# imu_evo.net
KiCad netlist of a schematic drawn in Altium Designer
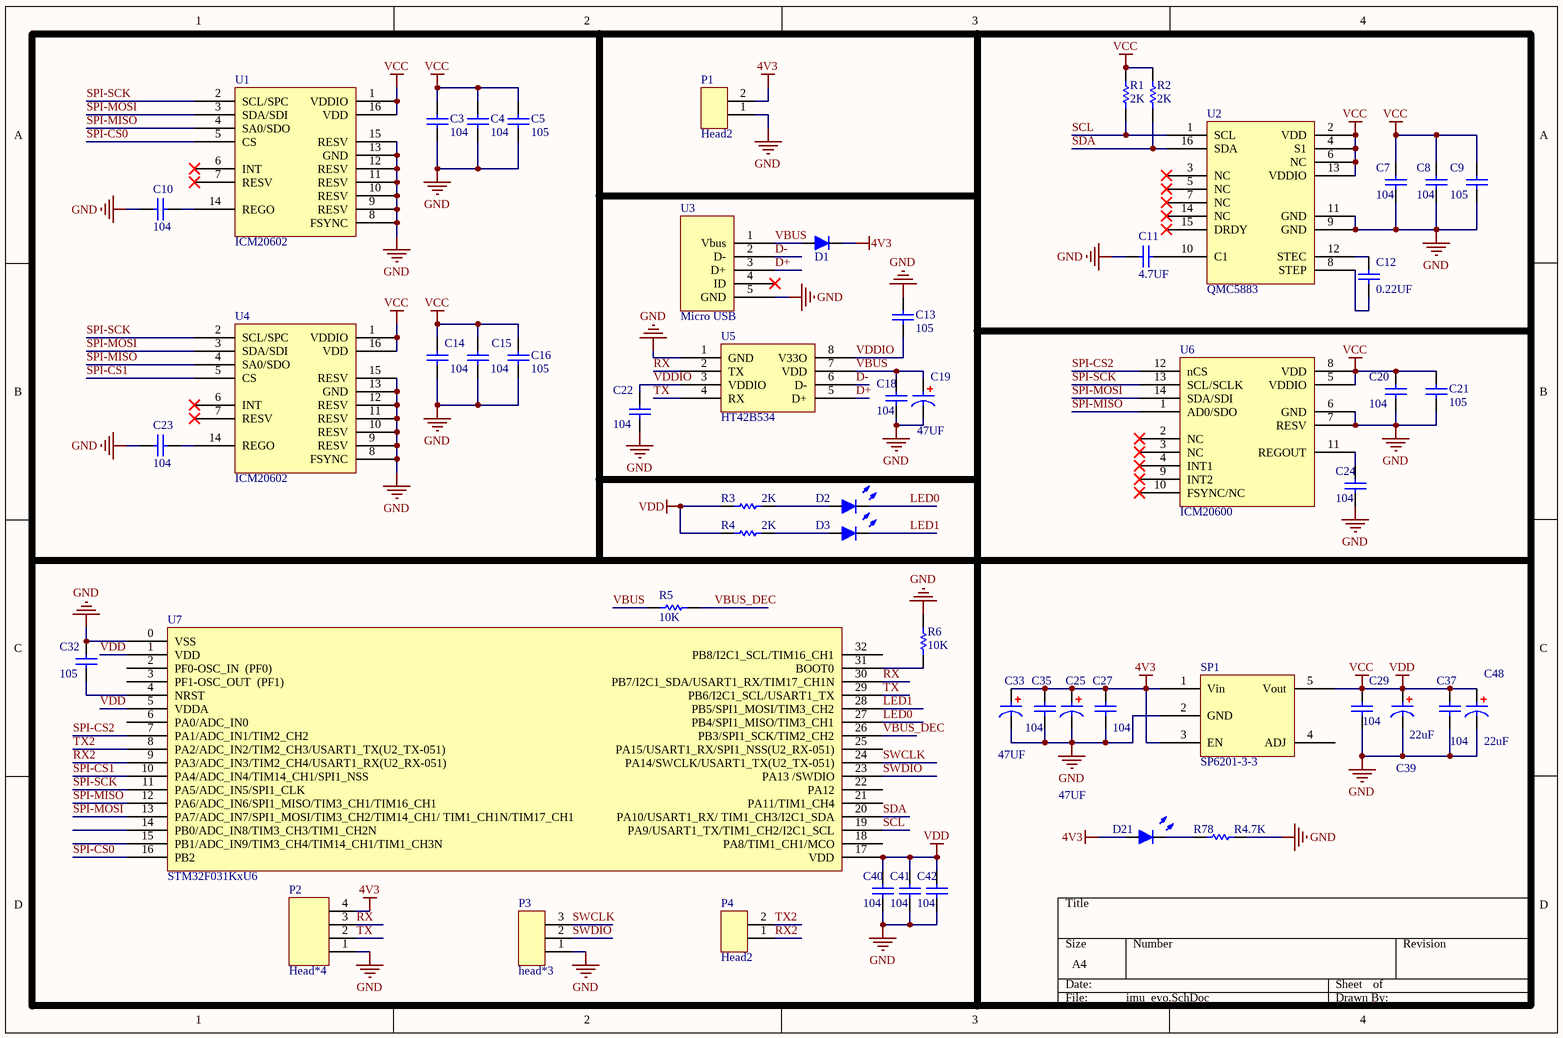
[diagram p0: imu_evo.SchDoc]

(export (version "E")
  (design (tool "Eeschema 10.0.6"))
  (components
    (comp (ref "C3")
      (value "104")
      (footprint "0402")
      (fields (field (name "ALTIUM_UNNAMED_1") "104"))
      (libsource (lib "OKmeSchLibrary") (part "C0.1uF"))
    )
    (comp (ref "C4")
      (value "104")
      (footprint "0402")
      (fields (field (name "ALTIUM_UNNAMED_1") "104"))
      (libsource (lib "OKmeSchLibrary") (part "C0.1uF"))
    )
    (comp (ref "C5")
      (value "C1uF")
      (footprint "0603C")
      (fields (field (name "ALTIUM_UNNAMED_1") "105"))
      (libsource (lib "OKmeSchLibrary") (part "C0.1uF"))
    )
    (comp (ref "C7")
      (value "104")
      (footprint "0402")
      (fields (field (name "ALTIUM_UNNAMED_1") "104"))
      (libsource (lib "OKmeSchLibrary") (part "C0.1uF"))
    )
    (comp (ref "C8")
      (value "104")
      (footprint "0402")
      (fields (field (name "ALTIUM_UNNAMED_1") "104"))
      (libsource (lib "OKmeSchLibrary") (part "C0.1uF"))
    )
    (comp (ref "C9")
      (value "C1uF")
      (footprint "0603C")
      (fields (field (name "ALTIUM_UNNAMED_1") "105"))
      (libsource (lib "OKmeSchLibrary") (part "C0.1uF"))
    )
    (comp (ref "C10")
      (value "104")
      (footprint "0402")
      (fields (field (name "ALTIUM_UNNAMED_1") "104"))
      (libsource (lib "OKmeSchLibrary") (part "C0.1uF"))
    )
    (comp (ref "C11")
      (value "4.7UF")
      (footprint "0603C")
      (fields (field (name "ALTIUM_UNNAMED_1") "4.7UF"))
      (libsource (lib "OKmeSchLibrary") (part "C0.1uF"))
    )
    (comp (ref "C12")
      (value "0.22UF")
      (footprint "0402")
      (fields (field (name "ALTIUM_UNNAMED_1") "0.22UF"))
      (libsource (lib "OKmeSchLibrary") (part "C0.1uF"))
    )
    (comp (ref "C13")
      (value "105")
      (footprint "0603C")
      (fields (field (name "ALTIUM_UNNAMED_1") "105"))
      (libsource (lib "OKmeSchLibrary") (part "C0.1uF"))
    )
    (comp (ref "C14")
      (value "104")
      (footprint "0402")
      (fields (field (name "ALTIUM_UNNAMED_1") "104"))
      (libsource (lib "OKmeSchLibrary") (part "C0.1uF"))
    )
    (comp (ref "C15")
      (value "104")
      (footprint "0402")
      (fields (field (name "ALTIUM_UNNAMED_1") "104"))
      (libsource (lib "OKmeSchLibrary") (part "C0.1uF"))
    )
    (comp (ref "C16")
      (value "C1uF")
      (footprint "0603C")
      (fields (field (name "ALTIUM_UNNAMED_1") "105"))
      (libsource (lib "OKmeSchLibrary") (part "C0.1uF"))
    )
    (comp (ref "C18")
      (value "104")
      (footprint "0402")
      (fields (field (name "ALTIUM_UNNAMED_1") "104"))
      (libsource (lib "OKmeSchLibrary") (part "C0.1uF"))
    )
    (comp (ref "C19")
      (value "47UF")
      (footprint "1206")
      (fields (field (name "ALTIUM_UNNAMED_1") "47UF"))
      (libsource (lib "OKmeSchLibrary") (part "C100uF"))
    )
    (comp (ref "C20")
      (value "104")
      (footprint "0402")
      (fields (field (name "ALTIUM_UNNAMED_1") "104"))
      (libsource (lib "OKmeSchLibrary") (part "C0.1uF"))
    )
    (comp (ref "C21")
      (value "C1uF")
      (footprint "0603C")
      (fields (field (name "ALTIUM_UNNAMED_1") "105"))
      (libsource (lib "OKmeSchLibrary") (part "C0.1uF"))
    )
    (comp (ref "C22")
      (value "104")
      (footprint "0402")
      (fields (field (name "ALTIUM_UNNAMED_1") "104"))
      (libsource (lib "OKmeSchLibrary") (part "C0.1uF"))
    )
    (comp (ref "C23")
      (value "104")
      (footprint "0402")
      (fields (field (name "ALTIUM_UNNAMED_1") "104"))
      (libsource (lib "OKmeSchLibrary") (part "C0.1uF"))
    )
    (comp (ref "C24")
      (value "104")
      (footprint "0402")
      (fields (field (name "ALTIUM_UNNAMED_1") "104"))
      (libsource (lib "OKmeSchLibrary") (part "C0.1uF"))
    )
    (comp (ref "C25")
      (value "47UF")
      (footprint "1206")
      (fields (field (name "ALTIUM_UNNAMED_1") "47UF"))
      (libsource (lib "OKmeSchLibrary") (part "C100uF"))
    )
    (comp (ref "C27")
      (value "104")
      (footprint "0603C")
      (fields (field (name "ALTIUM_UNNAMED_1") "104"))
      (libsource (lib "OKmeSchLibrary") (part "C0.1uF"))
    )
    (comp (ref "C29")
      (value "104")
      (footprint "0402")
      (fields (field (name "ALTIUM_UNNAMED_1") "104"))
      (libsource (lib "OKmeSchLibrary") (part "C0.1uF"))
    )
    (comp (ref "C32")
      (value "C1uF")
      (footprint "0603C")
      (fields (field (name "ALTIUM_UNNAMED_1") "105"))
      (libsource (lib "OKmeSchLibrary") (part "C0.1uF"))
    )
    (comp (ref "C33")
      (value "47UF")
      (footprint "1206")
      (fields (field (name "ALTIUM_UNNAMED_1") "47UF"))
      (libsource (lib "OKmeSchLibrary") (part "C100uF"))
    )
    (comp (ref "C35")
      (value "104")
      (footprint "0603C")
      (fields (field (name "ALTIUM_UNNAMED_1") "104"))
      (libsource (lib "OKmeSchLibrary") (part "C0.1uF"))
    )
    (comp (ref "C37")
      (value "104")
      (footprint "0402")
      (fields (field (name "ALTIUM_UNNAMED_1") "104"))
      (libsource (lib "OKmeSchLibrary") (part "C0.1uF"))
    )
    (comp (ref "C39")
      (value "22uF")
      (footprint "0603C")
      (fields (field (name "ALTIUM_UNNAMED_1") "22uF"))
      (libsource (lib "OKmeSchLibrary") (part "C100uF"))
    )
    (comp (ref "C40")
      (value "104")
      (footprint "0402")
      (fields (field (name "ALTIUM_UNNAMED_1") "104"))
      (libsource (lib "OKmeSchLibrary") (part "C0.1uF"))
    )
    (comp (ref "C41")
      (value "104")
      (footprint "0402")
      (fields (field (name "ALTIUM_UNNAMED_1") "104"))
      (libsource (lib "OKmeSchLibrary") (part "C0.1uF"))
    )
    (comp (ref "C42")
      (value "104")
      (footprint "0402")
      (fields (field (name "ALTIUM_UNNAMED_1") "104"))
      (libsource (lib "OKmeSchLibrary") (part "C0.1uF"))
    )
    (comp (ref "C48")
      (value "22uF")
      (footprint "0603C")
      (fields (field (name "ALTIUM_UNNAMED_1") "22uF"))
      (libsource (lib "OKmeSchLibrary") (part "C100uF"))
    )
    (comp (ref "D1")
      (value "BAT54WS")
      (footprint "LC-SOD-323F")
      (libsource (lib "OKmeSchLibrary") (part "Diode"))
    )
    (comp (ref "D2") (value "LED-G") (footprint "LED") (libsource (lib "OKmeSchLibrary") (part "LED")))
    (comp (ref "D3") (value "LED-B") (footprint "LED") (libsource (lib "OKmeSchLibrary") (part "LED")))
    (comp (ref "D21") (value "LED-R") (footprint "LED") (libsource (lib "OKmeSchLibrary") (part "LED")))
    (comp (ref "P1") (value "Head2") (footprint "HEAD2") (libsource (lib "OKmeSchLibrary") (part "Head2")))
    (comp (ref "P2")
      (value "Head*4")
      (footprint "B2BC-1.0-4P")
      (libsource (lib "OKmeSchLibrary") (part "Head*4"))
    )
    (comp (ref "P3")
      (value "head*3")
      (footprint "head*3 - duplicate")
      (libsource (lib "OKmeSchLibrary") (part "head*3"))
    )
    (comp (ref "P4") (value "Head2") (footprint "HEAD2") (libsource (lib "OKmeSchLibrary") (part "Head2")))
    (comp (ref "R1")
      (value "R2K")
      (footprint "0402")
      (fields (field (name "ALTIUM_UNNAMED_1") "2K"))
      (libsource (lib "OKmeSchLibrary") (part "R10K"))
    )
    (comp (ref "R2")
      (value "R2K")
      (footprint "0402")
      (fields (field (name "ALTIUM_UNNAMED_1") "2K"))
      (libsource (lib "OKmeSchLibrary") (part "R10K"))
    )
    (comp (ref "R3")
      (value "R2K")
      (footprint "0402")
      (fields (field (name "ALTIUM_UNNAMED_1") "2K"))
      (libsource (lib "OKmeSchLibrary") (part "R10K"))
    )
    (comp (ref "R4")
      (value "R2K")
      (footprint "0402")
      (fields (field (name "ALTIUM_UNNAMED_1") "2K"))
      (libsource (lib "OKmeSchLibrary") (part "R10K"))
    )
    (comp (ref "R5")
      (value "R10K")
      (footprint "0402")
      (fields (field (name "ALTIUM_UNNAMED_1") "10K"))
      (libsource (lib "OKmeSchLibrary") (part "R10K"))
    )
    (comp (ref "R6")
      (value "R10K")
      (footprint "0402")
      (fields (field (name "ALTIUM_UNNAMED_1") "10K"))
      (libsource (lib "OKmeSchLibrary") (part "R10K"))
    )
    (comp (ref "R78")
      (value "R4.7K")
      (footprint "0402")
      (fields (field (name "ALTIUM_UNNAMED_1") "R4.7K"))
      (libsource (lib "OKmeSchLibrary") (part "R10K"))
    )
    (comp (ref "SP1")
      (value "SP6201-3-3")
      (footprint "SOT23-5")
      (libsource (lib "OKmeSchLibrary") (part "SP6201"))
    )
    (comp (ref "U1") (value "ICM20602") (footprint "LGA16") (libsource (lib "imus") (part "ICM20602")))
    (comp (ref "U2") (value "QMC5883") (footprint "LGA16-Quad") (libsource (lib "imus") (part "QMC5883")))
    (comp (ref "U3")
      (value "Micro USB")
      (footprint "Micro_USB_t")
      (libsource (lib "OKmeSchLibrary") (part "MINI USB"))
    )
    (comp (ref "U4") (value "ICM20602") (footprint "LGA16") (libsource (lib "imus") (part "ICM20602")))
    (comp (ref "U5")
      (value "HT42B534")
      (footprint "SOP-8")
      (libsource (lib "OKmeSchLibrary") (part "HT42B534"))
    )
    (comp (ref "U6") (value "ICM20600") (footprint "LGA14") (libsource (lib "imus") (part "ICM20600")))
    (comp (ref "U7")
      (value "STM32F031KxU6")
      (footprint "QFN32")
      (libsource (lib "OKmeSchLibrary") (part "STM32F031KxU6"))
    )
  )
  (nets
    (net (code "1") (name "/D+") (class "Default")
      (node (ref "U3") (pin "3") (pinfunction "D+_3") (pintype "passive"))
      (node (ref "U5") (pin "5") (pinfunction "D+_5") (pintype "passive"))
    )
    (net (code "2") (name "/D-") (class "Default")
      (node (ref "U3") (pin "2") (pinfunction "D-_2") (pintype "passive"))
      (node (ref "U5") (pin "6") (pinfunction "D-_6") (pintype "passive"))
    )
    (net (code "3") (name "/LED0") (class "Default")
      (node (ref "D2") (pin "2") (pinfunction "K_2") (pintype "passive"))
      (node (ref "U7") (pin "27") (pinfunction "PB4/SPI1_MISO/TIM3_CH1_27") (pintype "passive"))
    )
    (net (code "4") (name "/LED1") (class "Default")
      (node (ref "D3") (pin "2") (pinfunction "K_2") (pintype "passive"))
      (node (ref "U7") (pin "28") (pinfunction "PB5/SPI1_MOSI/TIM3_CH2_28") (pintype "passive"))
    )
    (net (code "5") (name "/RX") (class "Default")
      (node (ref "P2") (pin "3") (pinfunction "3_3") (pintype "passive"))
      (node (ref "U5") (pin "2") (pinfunction "TX_2") (pintype "passive"))
      (node (ref "U7") (pin "30") (pinfunction "PB7/I2C1_SDA/USART1_RX/TIM17_CH1N_30") (pintype "passive"))
    )
    (net (code "6") (name "/RX2") (class "Default")
      (node (ref "P4") (pin "1") (pinfunction "1_1") (pintype "passive"))
      (node (ref "U7") (pin "9") (pinfunction "PA3/ADC_IN3/TIM2_CH4/USART1_RX(U2_RX-051)_9") (pintype "passive"))
    )
    (net (code "7") (name "/SCL") (class "Default")
      (node (ref "R1") (pin "1") (pinfunction "1_1") (pintype "passive"))
      (node (ref "U2") (pin "1") (pinfunction "SCL_1") (pintype "passive"))
      (node (ref "U7") (pin "19") (pinfunction "PA9/USART1_TX/TIM1_CH2/I2C1_SCL_19") (pintype "passive"))
    )
    (net (code "8") (name "/SDA") (class "Default")
      (node (ref "R2") (pin "1") (pinfunction "1_1") (pintype "passive"))
      (node (ref "U2") (pin "16") (pinfunction "SDA_16") (pintype "passive"))
      (node (ref "U7") (pin "20") (pinfunction "PA10/USART1_RX/_TIM1_CH3/I2C1_SDA_20") (pintype "passive"))
    )
    (net (code "9") (name "/SPI-CS0") (class "Default")
      (node (ref "U1") (pin "5") (pinfunction "CS_5") (pintype "passive"))
      (node (ref "U7") (pin "16") (pinfunction "PB2_16") (pintype "passive"))
    )
    (net (code "10") (name "/SPI-CS1") (class "Default")
      (node (ref "U4") (pin "5") (pinfunction "CS_5") (pintype "passive"))
      (node (ref "U7") (pin "10") (pinfunction "PA4/ADC_IN4/TIM14_CH1/SPI1_NSS_10") (pintype "passive"))
    )
    (net (code "11") (name "/SPI-CS2") (class "Default")
      (node (ref "U6") (pin "12") (pinfunction "nCS_12") (pintype "passive"))
      (node (ref "U7") (pin "7") (pinfunction "PA1/ADC_IN1/TIM2_CH2_7") (pintype "passive"))
    )
    (net (code "12") (name "/SPI-MISO") (class "Default")
      (node (ref "U1") (pin "4") (pinfunction "SA0/SDO_4") (pintype "passive"))
      (node (ref "U4") (pin "4") (pinfunction "SA0/SDO_4") (pintype "passive"))
      (node (ref "U6") (pin "1") (pinfunction "AD0/SDO_1") (pintype "passive"))
      (node (ref "U7") (pin "12") (pinfunction "PA6/ADC_IN6/SPI1_MISO/TIM3_CH1/TIM16_CH1_12") (pintype "passive"))
    )
    (net (code "13") (name "/SPI-MOSI") (class "Default")
      (node (ref "U1") (pin "3") (pinfunction "SDA/SDI_3") (pintype "passive"))
      (node (ref "U4") (pin "3") (pinfunction "SDA/SDI_3") (pintype "passive"))
      (node (ref "U6") (pin "14") (pinfunction "SDA/SDI_14") (pintype "passive"))
      (node (ref "U7") (pin "13") (pinfunction "PA7/ADC_IN7/SPI1_MOSI/TIM3_CH2/TIM14_CH1/_TIM1_CH1N/TIM17_CH1_13") (pintype "passive"))
    )
    (net (code "14") (name "/SPI-SCK") (class "Default")
      (node (ref "U1") (pin "2") (pinfunction "SCL/SPC_2") (pintype "passive"))
      (node (ref "U4") (pin "2") (pinfunction "SCL/SPC_2") (pintype "passive"))
      (node (ref "U6") (pin "13") (pinfunction "SCL/SCLK_13") (pintype "passive"))
      (node (ref "U7") (pin "11") (pinfunction "PA5/ADC_IN5/SPI1_CLK_11") (pintype "passive"))
    )
    (net (code "15") (name "/SWCLK") (class "Default")
      (node (ref "P3") (pin "3") (pinfunction "3_3") (pintype "passive"))
      (node (ref "U7") (pin "24") (pinfunction "PA14/SWCLK/USART1_TX(U2_TX-051)_24") (pintype "passive"))
    )
    (net (code "16") (name "/SWDIO") (class "Default")
      (node (ref "P3") (pin "2") (pinfunction "2_2") (pintype "passive"))
      (node (ref "U7") (pin "23") (pinfunction "PA13_/SWDIO_23") (pintype "passive"))
    )
    (net (code "17") (name "/TX") (class "Default")
      (node (ref "P2") (pin "2") (pinfunction "2_2") (pintype "passive"))
      (node (ref "U5") (pin "4") (pinfunction "RX_4") (pintype "passive"))
      (node (ref "U7") (pin "29") (pinfunction "PB6/I2C1_SCL/USART1_TX_29") (pintype "passive"))
    )
    (net (code "18") (name "/TX2") (class "Default")
      (node (ref "P4") (pin "2") (pinfunction "2_2") (pintype "passive"))
      (node (ref "U7") (pin "8") (pinfunction "PA2/ADC_IN2/TIM2_CH3/USART1_TX(U2_TX-051)_8") (pintype "passive"))
    )
    (net (code "19") (name "/VBUS") (class "Default")
      (node (ref "C18") (pin "1") (pinfunction "1_1") (pintype "passive"))
      (node (ref "C19") (pin "1") (pinfunction "1_1") (pintype "passive"))
      (node (ref "D1") (pin "1") (pinfunction "A_1") (pintype "passive"))
      (node (ref "R5") (pin "2") (pinfunction "2_2") (pintype "passive"))
      (node (ref "U3") (pin "1") (pinfunction "Vbus_1") (pintype "power_in"))
      (node (ref "U5") (pin "7") (pinfunction "VDD_7") (pintype "passive"))
    )
    (net (code "20") (name "/VBUS_DEC") (class "Default")
      (node (ref "R5") (pin "1") (pinfunction "1_1") (pintype "passive"))
      (node (ref "U7") (pin "26") (pinfunction "PB3/SPI1_SCK/TIM2_CH2_26") (pintype "passive"))
    )
    (net (code "21") (name "/VDDIO") (class "Default")
      (node (ref "C13") (pin "2") (pinfunction "2_2") (pintype "passive"))
      (node (ref "C22") (pin "1") (pinfunction "1_1") (pintype "passive"))
      (node (ref "U5") (pin "3") (pinfunction "VDDIO_3") (pintype "passive"))
      (node (ref "U5") (pin "8") (pinfunction "V33O_8") (pintype "passive"))
    )
    (net (code "22") (name "4V3") (class "Default")
      (node (ref "C25") (pin "1") (pinfunction "1_1") (pintype "passive"))
      (node (ref "C27") (pin "2") (pinfunction "2_2") (pintype "passive"))
      (node (ref "C33") (pin "1") (pinfunction "1_1") (pintype "passive"))
      (node (ref "C35") (pin "2") (pinfunction "2_2") (pintype "passive"))
      (node (ref "D1") (pin "2") (pinfunction "K_2") (pintype "passive"))
      (node (ref "D21") (pin "1") (pinfunction "A_1") (pintype "passive"))
      (node (ref "P1") (pin "2") (pinfunction "2_2") (pintype "passive"))
      (node (ref "P2") (pin "4") (pinfunction "4_4") (pintype "passive"))
      (node (ref "SP1") (pin "1") (pinfunction "Vin_1") (pintype "power_in"))
      (node (ref "SP1") (pin "3") (pinfunction "EN_3") (pintype "passive"))
    )
    (net (code "23") (name "GND") (class "Default")
      (node (ref "C10") (pin "1") (pinfunction "1_1") (pintype "passive"))
      (node (ref "C11") (pin "2") (pinfunction "2_2") (pintype "passive"))
      (node (ref "C13") (pin "1") (pinfunction "1_1") (pintype "passive"))
      (node (ref "C14") (pin "2") (pinfunction "2_2") (pintype "passive"))
      (node (ref "C15") (pin "2") (pinfunction "2_2") (pintype "passive"))
      (node (ref "C16") (pin "1") (pinfunction "1_1") (pintype "passive"))
      (node (ref "C18") (pin "2") (pinfunction "2_2") (pintype "passive"))
      (node (ref "C19") (pin "2") (pinfunction "2_2") (pintype "passive"))
      (node (ref "C20") (pin "2") (pinfunction "2_2") (pintype "passive"))
      (node (ref "C21") (pin "1") (pinfunction "1_1") (pintype "passive"))
      (node (ref "C22") (pin "2") (pinfunction "2_2") (pintype "passive"))
      (node (ref "C23") (pin "1") (pinfunction "1_1") (pintype "passive"))
      (node (ref "C24") (pin "2") (pinfunction "2_2") (pintype "passive"))
      (node (ref "C25") (pin "2") (pinfunction "2_2") (pintype "passive"))
      (node (ref "C27") (pin "1") (pinfunction "1_1") (pintype "passive"))
      (node (ref "C29") (pin "1") (pinfunction "1_1") (pintype "passive"))
      (node (ref "C3") (pin "2") (pinfunction "2_2") (pintype "passive"))
      (node (ref "C32") (pin "1") (pinfunction "1_1") (pintype "passive"))
      (node (ref "C33") (pin "2") (pinfunction "2_2") (pintype "passive"))
      (node (ref "C35") (pin "1") (pinfunction "1_1") (pintype "passive"))
      (node (ref "C37") (pin "1") (pinfunction "1_1") (pintype "passive"))
      (node (ref "C39") (pin "2") (pinfunction "2_2") (pintype "passive"))
      (node (ref "C4") (pin "2") (pinfunction "2_2") (pintype "passive"))
      (node (ref "C40") (pin "2") (pinfunction "2_2") (pintype "passive"))
      (node (ref "C41") (pin "2") (pinfunction "2_2") (pintype "passive"))
      (node (ref "C42") (pin "2") (pinfunction "2_2") (pintype "passive"))
      (node (ref "C48") (pin "2") (pinfunction "2_2") (pintype "passive"))
      (node (ref "C5") (pin "1") (pinfunction "1_1") (pintype "passive"))
      (node (ref "C7") (pin "2") (pinfunction "2_2") (pintype "passive"))
      (node (ref "C8") (pin "2") (pinfunction "2_2") (pintype "passive"))
      (node (ref "C9") (pin "1") (pinfunction "1_1") (pintype "passive"))
      (node (ref "P1") (pin "1") (pinfunction "1_1") (pintype "passive"))
      (node (ref "P2") (pin "1") (pinfunction "1_1") (pintype "passive"))
      (node (ref "P3") (pin "1") (pinfunction "1_1") (pintype "passive"))
      (node (ref "R6") (pin "2") (pinfunction "2_2") (pintype "passive"))
      (node (ref "R78") (pin "2") (pinfunction "2_2") (pintype "passive"))
      (node (ref "SP1") (pin "2") (pinfunction "GND_2") (pintype "power_in"))
      (node (ref "U1") (pin "10") (pinfunction "RESV_10") (pintype "passive"))
      (node (ref "U1") (pin "11") (pinfunction "RESV_11") (pintype "passive"))
      (node (ref "U1") (pin "12") (pinfunction "RESV_12") (pintype "passive"))
      (node (ref "U1") (pin "13") (pinfunction "GND_13") (pintype "passive"))
      (node (ref "U1") (pin "15") (pinfunction "RESV_15") (pintype "passive"))
      (node (ref "U1") (pin "8") (pinfunction "FSYNC_8") (pintype "passive"))
      (node (ref "U1") (pin "9") (pinfunction "RESV_9") (pintype "passive"))
      (node (ref "U2") (pin "11") (pinfunction "GND_11") (pintype "passive"))
      (node (ref "U2") (pin "9") (pinfunction "GND_9") (pintype "passive"))
      (node (ref "U3") (pin "5") (pinfunction "GND_5") (pintype "power_in"))
      (node (ref "U4") (pin "10") (pinfunction "RESV_10") (pintype "passive"))
      (node (ref "U4") (pin "11") (pinfunction "RESV_11") (pintype "passive"))
      (node (ref "U4") (pin "12") (pinfunction "RESV_12") (pintype "passive"))
      (node (ref "U4") (pin "13") (pinfunction "GND_13") (pintype "passive"))
      (node (ref "U4") (pin "15") (pinfunction "RESV_15") (pintype "passive"))
      (node (ref "U4") (pin "8") (pinfunction "FSYNC_8") (pintype "passive"))
      (node (ref "U4") (pin "9") (pinfunction "RESV_9") (pintype "passive"))
      (node (ref "U5") (pin "1") (pinfunction "GND_1") (pintype "passive"))
      (node (ref "U6") (pin "6") (pinfunction "GND_6") (pintype "passive"))
      (node (ref "U6") (pin "7") (pinfunction "RESV_7") (pintype "passive"))
      (node (ref "U7") (pin "0") (pinfunction "VSS_0") (pintype "passive"))
    )
    (net (code "24") (name "Net-(D2-A)") (class "Default")
      (node (ref "D2") (pin "1") (pinfunction "A_1") (pintype "passive"))
      (node (ref "R3") (pin "2") (pinfunction "2_2") (pintype "passive"))
    )
    (net (code "25") (name "Net-(D3-A)") (class "Default")
      (node (ref "D3") (pin "1") (pinfunction "A_1") (pintype "passive"))
      (node (ref "R4") (pin "2") (pinfunction "2_2") (pintype "passive"))
    )
    (net (code "26") (name "Net-(D21-K)") (class "Default")
      (node (ref "D21") (pin "2") (pinfunction "K_2") (pintype "passive"))
      (node (ref "R78") (pin "1") (pinfunction "1_1") (pintype "passive"))
    )
    (net (code "27") (name "Net-(U1-REGO)") (class "Default")
      (node (ref "C10") (pin "2") (pinfunction "2_2") (pintype "passive"))
      (node (ref "U1") (pin "14") (pinfunction "REGO_14") (pintype "passive"))
    )
    (net (code "28") (name "Net-(U2-C1)") (class "Default")
      (node (ref "C11") (pin "1") (pinfunction "1_1") (pintype "passive"))
      (node (ref "U2") (pin "10") (pinfunction "C1_10") (pintype "passive"))
    )
    (net (code "29") (name "Net-(U2-STEC)") (class "Default")
      (node (ref "C12") (pin "1") (pinfunction "1_1") (pintype "passive"))
      (node (ref "U2") (pin "12") (pinfunction "STEC_12") (pintype "passive"))
    )
    (net (code "30") (name "Net-(U2-STEP)") (class "Default")
      (node (ref "C12") (pin "2") (pinfunction "2_2") (pintype "passive"))
      (node (ref "U2") (pin "8") (pinfunction "STEP_8") (pintype "passive"))
    )
    (net (code "31") (name "Net-(U4-REGO)") (class "Default")
      (node (ref "C23") (pin "2") (pinfunction "2_2") (pintype "passive"))
      (node (ref "U4") (pin "14") (pinfunction "REGO_14") (pintype "passive"))
    )
    (net (code "32") (name "Net-(U6-REGOUT)") (class "Default")
      (node (ref "C24") (pin "1") (pinfunction "1_1") (pintype "passive"))
      (node (ref "U6") (pin "11") (pinfunction "REGOUT_11") (pintype "passive"))
    )
    (net (code "33") (name "Net-(U7-BOOT0)") (class "Default")
      (node (ref "R6") (pin "1") (pinfunction "1_1") (pintype "passive"))
      (node (ref "U7") (pin "31") (pinfunction "BOOT0_31") (pintype "passive"))
    )
    (net (code "34") (name "Net-(U7-NRST)") (class "Default")
      (node (ref "C32") (pin "2") (pinfunction "2_2") (pintype "passive"))
      (node (ref "U7") (pin "4") (pinfunction "NRST_4") (pintype "passive"))
    )
    (net (code "35") (name "VCC") (class "Default")
      (node (ref "C14") (pin "1") (pinfunction "1_1") (pintype "passive"))
      (node (ref "C15") (pin "1") (pinfunction "1_1") (pintype "passive"))
      (node (ref "C16") (pin "2") (pinfunction "2_2") (pintype "passive"))
      (node (ref "C20") (pin "1") (pinfunction "1_1") (pintype "passive"))
      (node (ref "C21") (pin "2") (pinfunction "2_2") (pintype "passive"))
      (node (ref "C29") (pin "2") (pinfunction "2_2") (pintype "passive"))
      (node (ref "C3") (pin "1") (pinfunction "1_1") (pintype "passive"))
      (node (ref "C37") (pin "2") (pinfunction "2_2") (pintype "passive"))
      (node (ref "C39") (pin "1") (pinfunction "1_1") (pintype "passive"))
      (node (ref "C4") (pin "1") (pinfunction "1_1") (pintype "passive"))
      (node (ref "C40") (pin "1") (pinfunction "1_1") (pintype "passive"))
      (node (ref "C41") (pin "1") (pinfunction "1_1") (pintype "passive"))
      (node (ref "C42") (pin "1") (pinfunction "1_1") (pintype "passive"))
      (node (ref "C48") (pin "1") (pinfunction "1_1") (pintype "passive"))
      (node (ref "C5") (pin "2") (pinfunction "2_2") (pintype "passive"))
      (node (ref "C7") (pin "1") (pinfunction "1_1") (pintype "passive"))
      (node (ref "C8") (pin "1") (pinfunction "1_1") (pintype "passive"))
      (node (ref "C9") (pin "2") (pinfunction "2_2") (pintype "passive"))
      (node (ref "R1") (pin "2") (pinfunction "2_2") (pintype "passive"))
      (node (ref "R2") (pin "2") (pinfunction "2_2") (pintype "passive"))
      (node (ref "R3") (pin "1") (pinfunction "1_1") (pintype "passive"))
      (node (ref "R4") (pin "1") (pinfunction "1_1") (pintype "passive"))
      (node (ref "SP1") (pin "5") (pinfunction "Vout_5") (pintype "power_in"))
      (node (ref "U1") (pin "1") (pinfunction "VDDIO_1") (pintype "passive"))
      (node (ref "U1") (pin "16") (pinfunction "VDD_16") (pintype "passive"))
      (node (ref "U2") (pin "13") (pinfunction "VDDIO_13") (pintype "passive"))
      (node (ref "U2") (pin "2") (pinfunction "VDD_2") (pintype "passive"))
      (node (ref "U2") (pin "4") (pinfunction "S1_4") (pintype "passive"))
      (node (ref "U2") (pin "6") (pinfunction "NC_6") (pintype "passive"))
      (node (ref "U4") (pin "1") (pinfunction "VDDIO_1") (pintype "passive"))
      (node (ref "U4") (pin "16") (pinfunction "VDD_16") (pintype "passive"))
      (node (ref "U6") (pin "5") (pinfunction "VDDIO_5") (pintype "passive"))
      (node (ref "U6") (pin "8") (pinfunction "VDD_8") (pintype "passive"))
      (node (ref "U7") (pin "1") (pinfunction "VDD_1") (pintype "passive"))
      (node (ref "U7") (pin "17") (pinfunction "VDD_17") (pintype "passive"))
      (node (ref "U7") (pin "5") (pinfunction "VDDA_5") (pintype "passive"))
    )
    (net (code "36") (name "unconnected-(SP1-ADJ-Pad4)") (class "Default")
      (node (ref "SP1") (pin "4") (pinfunction "ADJ_4") (pintype "passive"))
    )
    (net (code "37") (name "unconnected-(U1-INT-Pad6)") (class "Default")
      (node (ref "U1") (pin "6") (pinfunction "INT_6") (pintype "passive+no_connect"))
    )
    (net (code "38") (name "unconnected-(U1-RESV-Pad7)") (class "Default")
      (node (ref "U1") (pin "7") (pinfunction "RESV_7") (pintype "passive+no_connect"))
    )
    (net (code "39") (name "unconnected-(U2-DRDY-Pad15)") (class "Default")
      (node (ref "U2") (pin "15") (pinfunction "DRDY_15") (pintype "passive+no_connect"))
    )
    (net (code "40") (name "unconnected-(U2-NC-Pad3)") (class "Default")
      (node (ref "U2") (pin "3") (pinfunction "NC_3") (pintype "passive+no_connect"))
    )
    (net (code "41") (name "unconnected-(U2-NC-Pad5)") (class "Default")
      (node (ref "U2") (pin "5") (pinfunction "NC_5") (pintype "passive+no_connect"))
    )
    (net (code "42") (name "unconnected-(U2-NC-Pad7)") (class "Default")
      (node (ref "U2") (pin "7") (pinfunction "NC_7") (pintype "passive+no_connect"))
    )
    (net (code "43") (name "unconnected-(U2-NC-Pad14)") (class "Default")
      (node (ref "U2") (pin "14") (pinfunction "NC_14") (pintype "passive+no_connect"))
    )
    (net (code "44") (name "unconnected-(U3-ID-Pad4)") (class "Default")
      (node (ref "U3") (pin "4") (pinfunction "ID_4") (pintype "passive+no_connect"))
    )
    (net (code "45") (name "unconnected-(U3-SHELL-Pad0)") (class "Default")
      (node (ref "U3") (pin "0") (pinfunction "SHELL_0") (pintype "passive"))
    )
    (net (code "46") (name "unconnected-(U4-INT-Pad6)") (class "Default")
      (node (ref "U4") (pin "6") (pinfunction "INT_6") (pintype "passive+no_connect"))
    )
    (net (code "47") (name "unconnected-(U4-RESV-Pad7)") (class "Default")
      (node (ref "U4") (pin "7") (pinfunction "RESV_7") (pintype "passive+no_connect"))
    )
    (net (code "48") (name "unconnected-(U6-FSYNC{slash}NC-Pad10)") (class "Default")
      (node (ref "U6") (pin "10") (pinfunction "FSYNC/NC_10") (pintype "passive+no_connect"))
    )
    (net (code "49") (name "unconnected-(U6-INT1-Pad4)") (class "Default")
      (node (ref "U6") (pin "4") (pinfunction "INT1_4") (pintype "passive+no_connect"))
    )
    (net (code "50") (name "unconnected-(U6-INT2-Pad9)") (class "Default")
      (node (ref "U6") (pin "9") (pinfunction "INT2_9") (pintype "passive+no_connect"))
    )
    (net (code "51") (name "unconnected-(U6-NC-Pad2)") (class "Default")
      (node (ref "U6") (pin "2") (pinfunction "NC_2") (pintype "passive+no_connect"))
    )
    (net (code "52") (name "unconnected-(U6-NC-Pad3)") (class "Default")
      (node (ref "U6") (pin "3") (pinfunction "NC_3") (pintype "passive+no_connect"))
    )
    (net (code "53") (name "unconnected-(U7-PA0{slash}ADC_IN0-Pad6)") (class "Default")
      (node (ref "U7") (pin "6") (pinfunction "PA0/ADC_IN0_6") (pintype "passive"))
    )
    (net (code "54") (name "unconnected-(U7-PA8{slash}TIM1_CH1{slash}MCO-Pad18)") (class "Default")
      (node (ref "U7") (pin "18") (pinfunction "PA8/TIM1_CH1/MCO_18") (pintype "passive"))
    )
    (net (code "55") (name "unconnected-(U7-PA11{slash}TIM1_CH4-Pad21)") (class "Default")
      (node (ref "U7") (pin "21") (pinfunction "PA11/TIM1_CH4_21") (pintype "passive"))
    )
    (net (code "56") (name "unconnected-(U7-PA12-Pad22)") (class "Default")
      (node (ref "U7") (pin "22") (pinfunction "PA12_22") (pintype "passive"))
    )
    (net (code "57") (name "unconnected-(U7-PA15{slash}USART1_RX{slash}SPI1_NSS(U2_RX-051)-Pad25)") (class "Default")
      (node (ref "U7") (pin "25") (pinfunction "PA15/USART1_RX/SPI1_NSS(U2_RX-051)_25") (pintype "passive"))
    )
    (net (code "58") (name "unconnected-(U7-PB0{slash}ADC_IN8{slash}TIM3_CH3{slash}TIM1_CH2N-Pad14)") (class "Default")
      (node (ref "U7") (pin "14") (pinfunction "PB0/ADC_IN8/TIM3_CH3/TIM1_CH2N_14") (pintype "passive"))
    )
    (net (code "59") (name "unconnected-(U7-PB1{slash}ADC_IN9{slash}TIM3_CH4{slash}TIM14_CH1{slash}TIM1_CH3N-Pad15)") (class "Default")
      (node (ref "U7") (pin "15") (pinfunction "PB1/ADC_IN9/TIM3_CH4/TIM14_CH1/TIM1_CH3N_15") (pintype "passive"))
    )
    (net (code "60") (name "unconnected-(U7-PB8{slash}I2C1_SCL{slash}TIM16_CH1-Pad32)") (class "Default")
      (node (ref "U7") (pin "32") (pinfunction "PB8/I2C1_SCL/TIM16_CH1_32") (pintype "passive"))
    )
    (net (code "61") (name "unconnected-(U7-PF0-OSC_IN__(PF0)-Pad2)") (class "Default")
      (node (ref "U7") (pin "2") (pinfunction "PF0-OSC_IN__(PF0)_2") (pintype "passive"))
    )
    (net (code "62") (name "unconnected-(U7-PF1-OSC_OUT__(PF1)-Pad3)") (class "Default")
      (node (ref "U7") (pin "3") (pinfunction "PF1-OSC_OUT__(PF1)_3") (pintype "passive"))
    )
  )
)
